# riffleBoost3V3.net
KiCad netlist of a schematic drawn in EAGLE
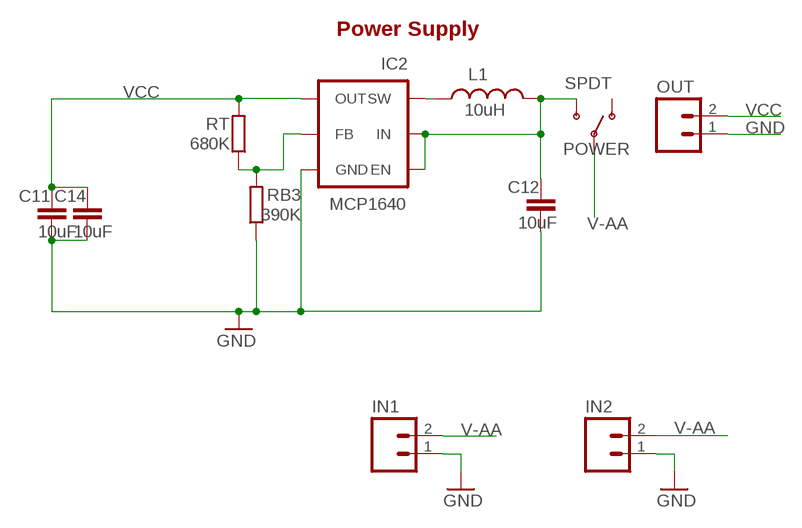
[diagram p0: schematic, sheet 1]

(export (version "E")
  (design (tool "Eeschema 10.0.6"))
  (components
    (comp (ref "C11")
      (value "10uF")
      (footprint "eagle-import:C0805")
      (libsource (lib "eagle-import") (part "C-EUC0805"))
    )
    (comp (ref "C12")
      (value "10uF")
      (footprint "eagle-import:C0805")
      (libsource (lib "eagle-import") (part "C-EUC0805"))
    )
    (comp (ref "C14")
      (value "10uF")
      (footprint "eagle-import:C0805")
      (libsource (lib "eagle-import") (part "C-EUC0805"))
    )
    (comp (ref "IC2")
      (value "MCP1640")
      (footprint "eagle-import:TSOT23-6")
      (libsource (lib "eagle-import") (part "MCP1640"))
    )
    (comp (ref "IN1")
      (value "M02PTH")
      (footprint "eagle-import:1X02")
      (libsource (lib "eagle-import") (part "M02PTH"))
    )
    (comp (ref "IN2")
      (value "M02-JST-2MM-SMT")
      (footprint "eagle-import:JST-2-SMD")
      (libsource (lib "eagle-import") (part "M02-JST-2MM-SMT"))
    )
    (comp (ref "L1")
      (value "10uH")
      (footprint "eagle-import:INDUCTOR_D30")
      (libsource (lib "eagle-import") (part "INDUCTOR_SMDD30"))
    )
    (comp (ref "OUT")
      (value "M021X02_NO_SILK")
      (footprint "eagle-import:1X02_NO_SILK")
      (libsource (lib "eagle-import") (part "M021X02_NO_SILK"))
    )
    (comp (ref "POWER")
      (value "SPDT")
      (footprint "eagle-import:SWITCH-SPDT-SMD")
      (libsource (lib "eagle-import") (part "SWITCH-SPSTSMD2"))
    )
    (comp (ref "RB3")
      (value "390K")
      (footprint "eagle-import:R0805")
      (libsource (lib "eagle-import") (part "R-EU_R0805"))
    )
    (comp (ref "RT")
      (value "680K")
      (footprint "eagle-import:R0805")
      (libsource (lib "eagle-import") (part "R-EU_R0805"))
    )
  )
  (nets
    (net (code "1") (name "/V-AA") (class "Default")
      (node (ref "IN1") (pin "2") (pinfunction "2_2") (pintype "passive"))
      (node (ref "IN2") (pin "2") (pinfunction "2_2") (pintype "passive"))
      (node (ref "POWER") (pin "2") (pinfunction "P_2") (pintype "passive"))
    )
    (net (code "2") (name "/VCC") (class "Default")
      (node (ref "C11") (pin "1") (pinfunction "1_1") (pintype "passive"))
      (node (ref "C14") (pin "1") (pinfunction "1_1") (pintype "passive"))
      (node (ref "IC2") (pin "5") (pinfunction "OUT_5") (pintype "passive"))
      (node (ref "OUT") (pin "2") (pinfunction "2_2") (pintype "passive"))
      (node (ref "RT") (pin "2") (pinfunction "2_2") (pintype "passive"))
    )
    (net (code "3") (name "GND") (class "Default")
      (node (ref "C11") (pin "2") (pinfunction "2_2") (pintype "passive"))
      (node (ref "C12") (pin "2") (pinfunction "2_2") (pintype "passive"))
      (node (ref "C14") (pin "2") (pinfunction "2_2") (pintype "passive"))
      (node (ref "IC2") (pin "2") (pinfunction "GND_2") (pintype "input"))
      (node (ref "IN1") (pin "1") (pinfunction "1_1") (pintype "passive"))
      (node (ref "IN2") (pin "1") (pinfunction "1_1") (pintype "passive"))
      (node (ref "OUT") (pin "1") (pinfunction "1_1") (pintype "passive"))
      (node (ref "RB3") (pin "1") (pinfunction "1_1") (pintype "passive"))
    )
    (net (code "4") (name "Net-(IC2-EN)") (class "Default")
      (node (ref "C12") (pin "1") (pinfunction "1_1") (pintype "passive"))
      (node (ref "IC2") (pin "3") (pinfunction "EN_3") (pintype "input"))
      (node (ref "IC2") (pin "6") (pinfunction "IN_6") (pintype "input"))
      (node (ref "L1") (pin "P$1") (pinfunction "1_P$1") (pintype "passive"))
      (node (ref "POWER") (pin "3") (pinfunction "S_3") (pintype "passive"))
    )
    (net (code "5") (name "Net-(IC2-FB)") (class "Default")
      (node (ref "IC2") (pin "4") (pinfunction "FB_4") (pintype "input"))
      (node (ref "RB3") (pin "2") (pinfunction "2_2") (pintype "passive"))
      (node (ref "RT") (pin "1") (pinfunction "1_1") (pintype "passive"))
    )
    (net (code "6") (name "Net-(IC2-SW)") (class "Default")
      (node (ref "IC2") (pin "1") (pinfunction "SW_1") (pintype "output"))
      (node (ref "L1") (pin "P$2") (pinfunction "2_P$2") (pintype "passive"))
    )
    (net (code "7") (name "unconnected-(POWER-O-Pad1)") (class "Default")
      (node (ref "POWER") (pin "1") (pinfunction "O_1") (pintype "passive"))
    )
  )
)
